# xmas_tree_pcb_B.net
KiCad netlist of a schematic drawn in EAGLE
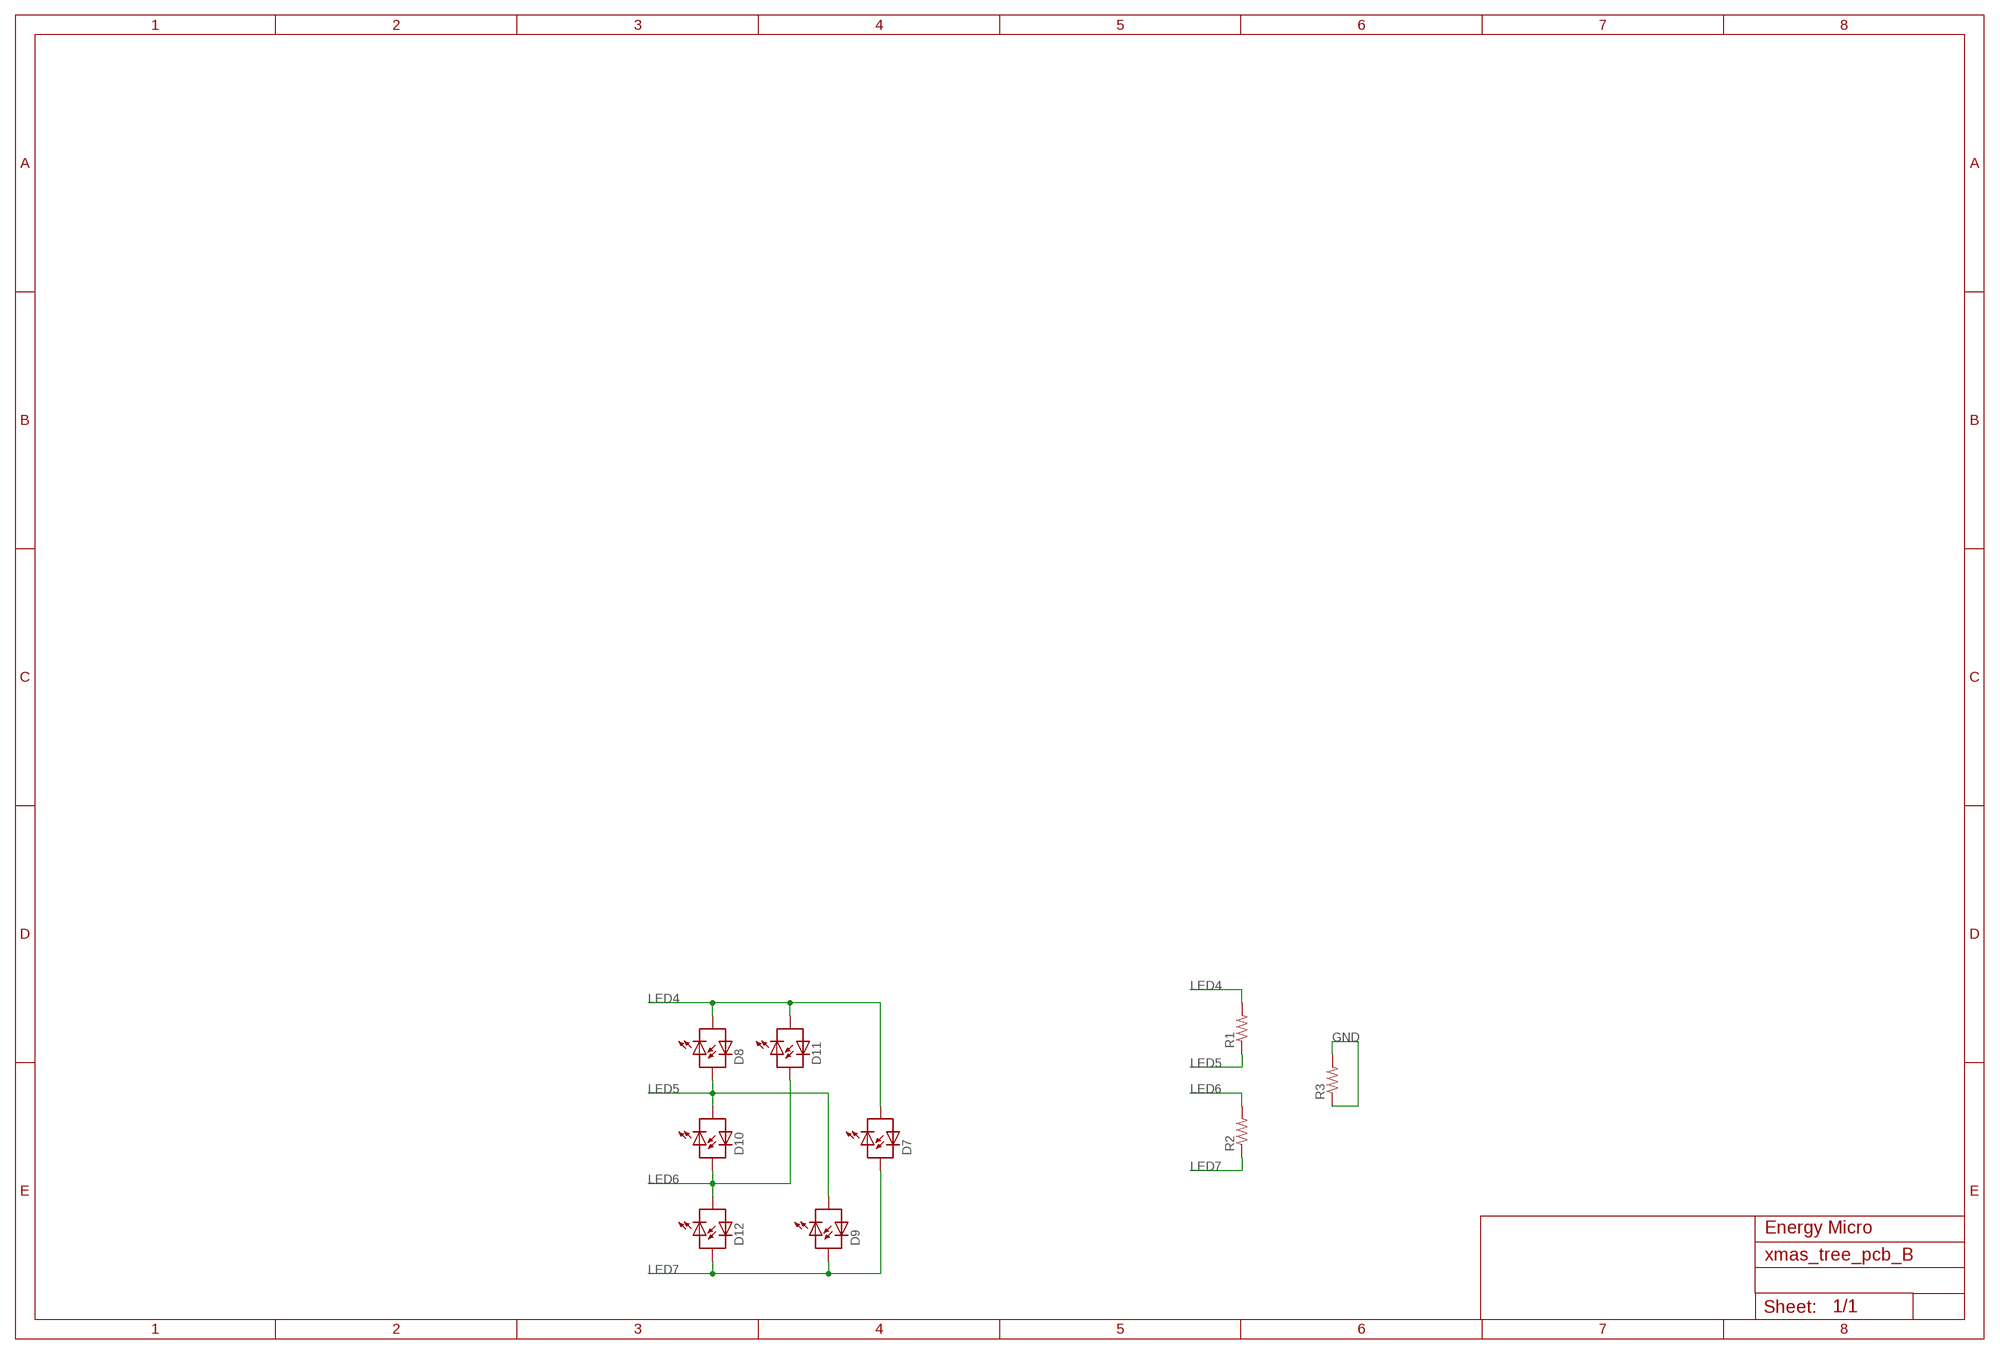
[diagram p0: schematic, sheet 1]

(export (version "E")
  (design (tool "Eeschema 10.0.6"))
  (components
    (comp (ref "D7")
      (value "LED_BI_COLOR")
      (footprint "eagle-import:LED3MM")
      (libsource (lib "eagle-import") (part "LED_BI_COLOR"))
    )
    (comp (ref "D8")
      (value "LED_BI_COLOR")
      (footprint "eagle-import:LED3MM")
      (libsource (lib "eagle-import") (part "LED_BI_COLOR"))
    )
    (comp (ref "D9")
      (value "LED_BI_COLOR")
      (footprint "eagle-import:LED3MM")
      (libsource (lib "eagle-import") (part "LED_BI_COLOR"))
    )
    (comp (ref "D10")
      (value "LED_BI_COLOR")
      (footprint "eagle-import:LED3MM")
      (libsource (lib "eagle-import") (part "LED_BI_COLOR"))
    )
    (comp (ref "D11")
      (value "LED_BI_COLOR")
      (footprint "eagle-import:LED3MM")
      (libsource (lib "eagle-import") (part "LED_BI_COLOR"))
    )
    (comp (ref "D12")
      (value "LED_BI_COLOR")
      (footprint "eagle-import:LED3MM")
      (libsource (lib "eagle-import") (part "LED_BI_COLOR"))
    )
    (comp (ref "R1")
      (value "RESISTOR1206")
      (footprint "eagle-import:1206")
      (libsource (lib "eagle-import") (part "RESISTOR1206"))
    )
    (comp (ref "R2")
      (value "RESISTOR1206")
      (footprint "eagle-import:1206")
      (libsource (lib "eagle-import") (part "RESISTOR1206"))
    )
    (comp (ref "R3")
      (value "RESISTOR1206")
      (footprint "eagle-import:1206")
      (libsource (lib "eagle-import") (part "RESISTOR1206"))
    )
  )
  (nets
    (net (code "1") (name "/GND") (class "Default")
      (node (ref "R3") (pin "1") (pinfunction "1_1") (pintype "passive"))
      (node (ref "R3") (pin "2") (pinfunction "2_2") (pintype "passive"))
    )
    (net (code "2") (name "/LED4") (class "Default")
      (node (ref "D11") (pin "K") (pinfunction "C1_K") (pintype "passive"))
      (node (ref "D7") (pin "K") (pinfunction "C1_K") (pintype "passive"))
      (node (ref "D8") (pin "K") (pinfunction "C1_K") (pintype "passive"))
      (node (ref "R1") (pin "2") (pinfunction "2_2") (pintype "passive"))
    )
    (net (code "3") (name "/LED5") (class "Default")
      (node (ref "D10") (pin "K") (pinfunction "C1_K") (pintype "passive"))
      (node (ref "D8") (pin "A") (pinfunction "A1_A") (pintype "passive"))
      (node (ref "D9") (pin "K") (pinfunction "C1_K") (pintype "passive"))
      (node (ref "R1") (pin "1") (pinfunction "1_1") (pintype "passive"))
    )
    (net (code "4") (name "/LED6") (class "Default")
      (node (ref "D10") (pin "A") (pinfunction "A1_A") (pintype "passive"))
      (node (ref "D11") (pin "A") (pinfunction "A1_A") (pintype "passive"))
      (node (ref "D12") (pin "K") (pinfunction "C1_K") (pintype "passive"))
      (node (ref "R2") (pin "2") (pinfunction "2_2") (pintype "passive"))
    )
    (net (code "5") (name "/LED7") (class "Default")
      (node (ref "D12") (pin "A") (pinfunction "A1_A") (pintype "passive"))
      (node (ref "D7") (pin "A") (pinfunction "A1_A") (pintype "passive"))
      (node (ref "D9") (pin "A") (pinfunction "A1_A") (pintype "passive"))
      (node (ref "R2") (pin "1") (pinfunction "1_1") (pintype "passive"))
    )
  )
)
